# ClosedLoop_Drive_UI_Display.net
KiCad netlist of a schematic drawn in Altium Designer
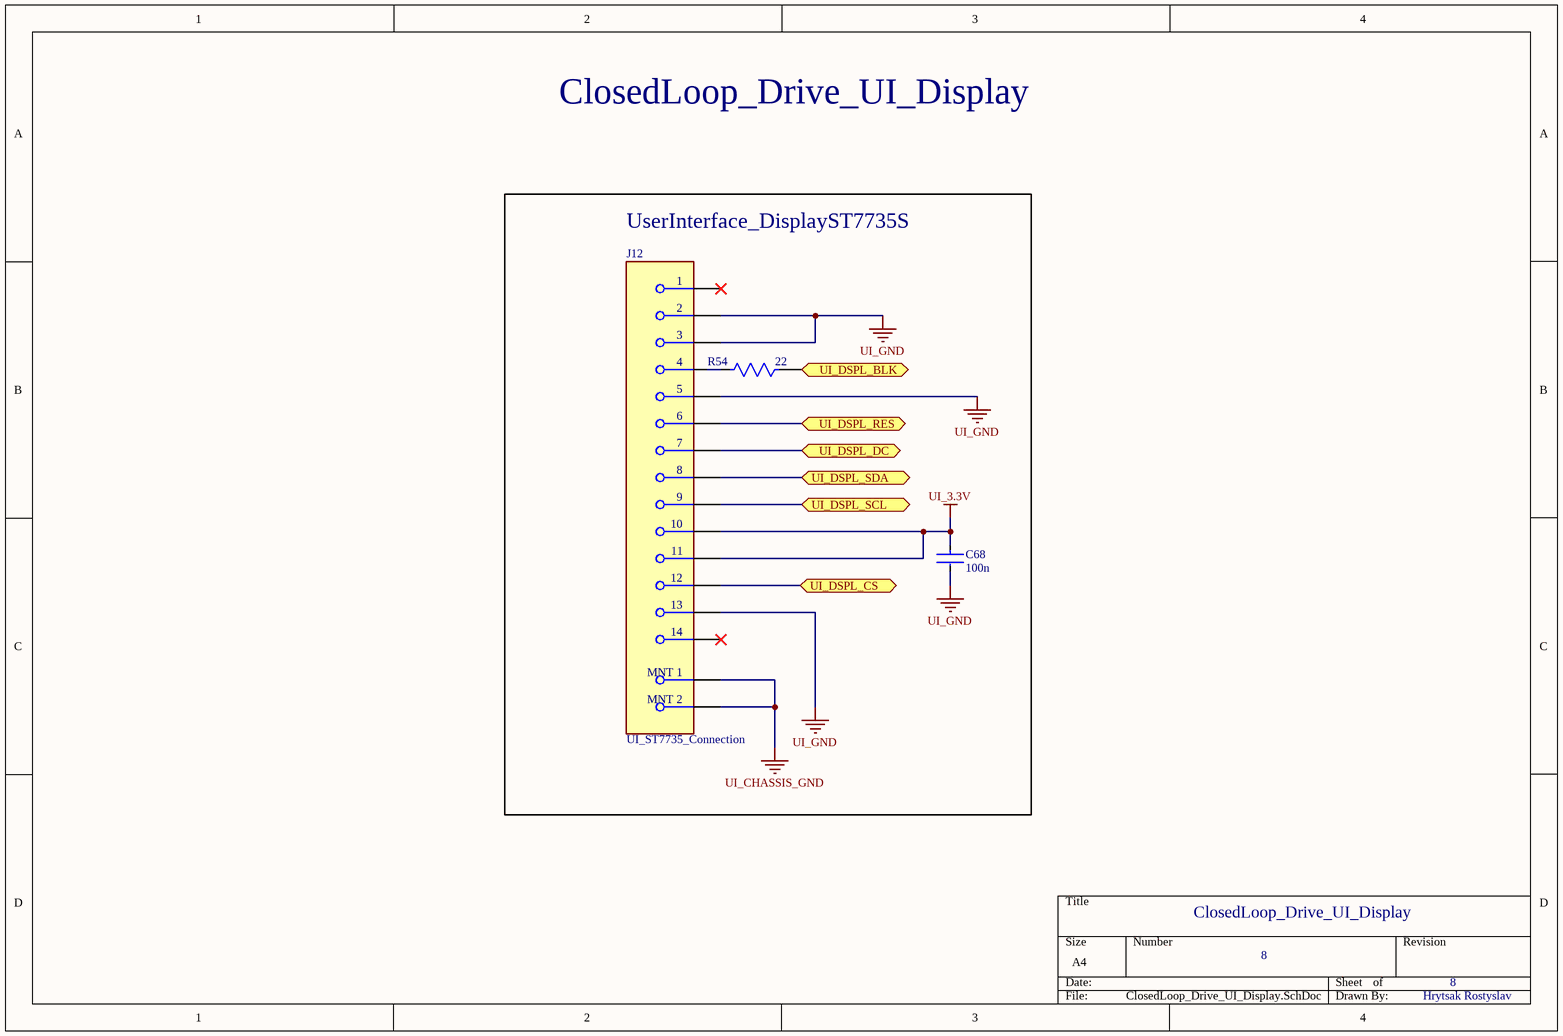
[diagram p0: ClosedLoop_Drive_UI_Display.SchDoc]

(export (version "E")
  (design (tool "Eeschema 10.0.6"))
  (components
    (comp (ref "C68")
      (value "100n")
      (footprint "FP-0805-L_2_01_0_2-W_1_25-MFG")
      (description "0805")
      (fields (field (name "TOLERANCE") "10%"))
      (libsource (lib "Altium Content Vault") (part "b4654b650e69147ec39a6b967a45e02"))
    )
    (comp (ref "J12")
      (value "UI_ST7735_Connection")
      (footprint "FP-TF31-14S-0_5SH_800-MFG")
      (description "CONN FFC 14POS 0.50MM SMD")
      (libsource (lib "Altium Content Vault") (part "aa7aa886286bd71ec26f205279876b1"))
    )
    (comp (ref "R54")
      (value "22")
      (footprint "FP-MCU0805-IPC_A")
      (description "0805")
      (fields (field (name "TOLERANCE") "0.5%"))
      (libsource (lib "Altium Content Vault") (part "1029c3af85768c4190bb7ad29bc67b5"))
    )
  )
  (nets
    (net (code "1") (name "/UI_DSPL_BLK") (class "Default")
      (node (ref "R54") (pin "1") (pinfunction "1_1") (pintype "passive"))
    )
    (net (code "2") (name "/UI_DSPL_CS") (class "Default")
      (node (ref "J12") (pin "12") (pinfunction "12_12") (pintype "passive"))
    )
    (net (code "3") (name "/UI_DSPL_DC") (class "Default")
      (node (ref "J12") (pin "7") (pinfunction "7_7") (pintype "passive"))
    )
    (net (code "4") (name "/UI_DSPL_RES") (class "Default")
      (node (ref "J12") (pin "6") (pinfunction "6_6") (pintype "passive"))
    )
    (net (code "5") (name "/UI_DSPL_SCL") (class "Default")
      (node (ref "J12") (pin "9") (pinfunction "9_9") (pintype "passive"))
    )
    (net (code "6") (name "/UI_DSPL_SDA") (class "Default")
      (node (ref "J12") (pin "8") (pinfunction "8_8") (pintype "passive"))
    )
    (net (code "7") (name "Net-(J12-Pad4)") (class "Default")
      (node (ref "J12") (pin "4") (pinfunction "4_4") (pintype "passive"))
      (node (ref "R54") (pin "2") (pinfunction "2_2") (pintype "passive"))
    )
    (net (code "8") (name "UI_3.3V") (class "Default")
      (node (ref "C68") (pin "1") (pinfunction "1_1") (pintype "passive"))
      (node (ref "J12") (pin "10") (pinfunction "10_10") (pintype "passive"))
      (node (ref "J12") (pin "11") (pinfunction "11_11") (pintype "passive"))
    )
    (net (code "9") (name "UI_CHASSIS_GND") (class "Default")
      (node (ref "J12") (pin "15") (pinfunction "MNT_1_15") (pintype "passive"))
      (node (ref "J12") (pin "16") (pinfunction "MNT_2_16") (pintype "passive"))
    )
    (net (code "10") (name "UI_GND") (class "Default")
      (node (ref "C68") (pin "2") (pinfunction "2_2") (pintype "passive"))
      (node (ref "J12") (pin "13") (pinfunction "13_13") (pintype "passive"))
      (node (ref "J12") (pin "2") (pinfunction "2_2") (pintype "passive"))
      (node (ref "J12") (pin "3") (pinfunction "3_3") (pintype "passive"))
      (node (ref "J12") (pin "5") (pinfunction "5_5") (pintype "passive"))
    )
    (net (code "11") (name "unconnected-(J12-Pad1)") (class "Default")
      (node (ref "J12") (pin "1") (pinfunction "1_1") (pintype "passive+no_connect"))
    )
    (net (code "12") (name "unconnected-(J12-Pad14)") (class "Default")
      (node (ref "J12") (pin "14") (pinfunction "14_14") (pintype "passive+no_connect"))
    )
  )
)
